# FLink_Unit.net
KiCad netlist of a schematic drawn in Altium Designer
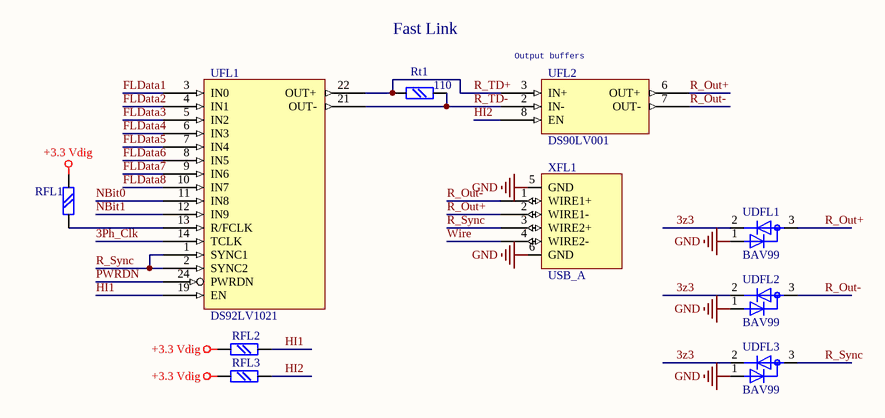
[diagram p0: FLink Unit.SchDoc]

(export (version "E")
  (design (tool "Eeschema 10.0.6"))
  (components
    (comp (ref "RFL1") (value "CHIP0805") (footprint "CHIP0805") (libsource (lib "*") (part "R")))
    (comp (ref "RFL2") (value "CHIP0805") (footprint "CHIP0805") (libsource (lib "*") (part "R")))
    (comp (ref "RFL3") (value "CHIP0805") (footprint "CHIP0805") (libsource (lib "*") (part "R")))
    (comp (ref "Rt1") (value "110") (footprint "CHIP0805") (libsource (lib "*") (part "R")))
    (comp (ref "UDFL1") (value "BAV99") (footprint "SOT-23") (libsource (lib "*") (part "BAV99")))
    (comp (ref "UDFL2") (value "BAV99") (footprint "SOT-23") (libsource (lib "*") (part "BAV99")))
    (comp (ref "UDFL3") (value "BAV99") (footprint "SOT-23") (libsource (lib "*") (part "BAV99")))
    (comp (ref "UFL1") (value "DS92LV1021") (footprint "28TSSOP") (libsource (lib "*") (part "DS92LV1021")))
    (comp (ref "UFL2") (value "DS90LV001") (footprint "Soic8_200") (libsource (lib "*") (part "DS90LV001")))
    (comp (ref "XFL1") (value "USB_A") (footprint "USB-A") (libsource (lib "*") (part "USB_A")))
  )
  (nets
    (net (code "1") (name "+3.3 Vdig") (class "Default")
      (node (ref "RFL1") (pin "2") (pinfunction "2_2") (pintype "passive"))
      (node (ref "RFL2") (pin "1") (pinfunction "1_1") (pintype "passive"))
      (node (ref "RFL3") (pin "1") (pinfunction "1_1") (pintype "passive"))
    )
    (net (code "2") (name "/3Ph_Clk") (class "Default")
      (node (ref "UFL1") (pin "14") (pinfunction "TCLK_14") (pintype "input"))
    )
    (net (code "3") (name "/3z3") (class "Default")
      (node (ref "UDFL1") (pin "2") (pinfunction "CATHODE_2") (pintype "passive"))
      (node (ref "UDFL2") (pin "2") (pinfunction "CATHODE_2") (pintype "passive"))
      (node (ref "UDFL3") (pin "2") (pinfunction "CATHODE_2") (pintype "passive"))
    )
    (net (code "4") (name "/FLData1") (class "Default")
      (node (ref "UFL1") (pin "3") (pinfunction "IN0_3") (pintype "input"))
    )
    (net (code "5") (name "/FLData2") (class "Default")
      (node (ref "UFL1") (pin "4") (pinfunction "IN1_4") (pintype "input"))
    )
    (net (code "6") (name "/FLData3") (class "Default")
      (node (ref "UFL1") (pin "5") (pinfunction "IN2_5") (pintype "input"))
    )
    (net (code "7") (name "/FLData4") (class "Default")
      (node (ref "UFL1") (pin "6") (pinfunction "IN3_6") (pintype "input"))
    )
    (net (code "8") (name "/FLData5") (class "Default")
      (node (ref "UFL1") (pin "7") (pinfunction "IN4_7") (pintype "input"))
    )
    (net (code "9") (name "/FLData6") (class "Default")
      (node (ref "UFL1") (pin "8") (pinfunction "IN5_8") (pintype "input"))
    )
    (net (code "10") (name "/FLData7") (class "Default")
      (node (ref "UFL1") (pin "9") (pinfunction "IN6_9") (pintype "input"))
    )
    (net (code "11") (name "/FLData8") (class "Default")
      (node (ref "UFL1") (pin "10") (pinfunction "IN7_10") (pintype "input"))
    )
    (net (code "12") (name "/HI1") (class "Default")
      (node (ref "RFL2") (pin "2") (pinfunction "2_2") (pintype "passive"))
      (node (ref "UFL1") (pin "19") (pinfunction "EN_19") (pintype "input"))
    )
    (net (code "13") (name "/HI2") (class "Default")
      (node (ref "RFL3") (pin "2") (pinfunction "2_2") (pintype "passive"))
      (node (ref "UFL2") (pin "8") (pinfunction "EN_8") (pintype "input"))
    )
    (net (code "14") (name "/NBit0") (class "Default")
      (node (ref "UFL1") (pin "11") (pinfunction "IN8_11") (pintype "input"))
    )
    (net (code "15") (name "/NBit1") (class "Default")
      (node (ref "UFL1") (pin "12") (pinfunction "IN9_12") (pintype "input"))
    )
    (net (code "16") (name "/PWRDN") (class "Default")
      (node (ref "UFL1") (pin "24") (pinfunction "PWRDN_24") (pintype "input"))
    )
    (net (code "17") (name "/R_Out+") (class "Default")
      (node (ref "UDFL1") (pin "3") (pinfunction "COMMON_3") (pintype "passive"))
      (node (ref "UFL2") (pin "6") (pinfunction "OUT+_6") (pintype "output"))
      (node (ref "XFL1") (pin "2") (pinfunction "WIRE1-_2") (pintype "bidirectional"))
    )
    (net (code "18") (name "/R_Out-") (class "Default")
      (node (ref "UDFL2") (pin "3") (pinfunction "COMMON_3") (pintype "passive"))
      (node (ref "UFL2") (pin "7") (pinfunction "OUT-_7") (pintype "output"))
      (node (ref "XFL1") (pin "1") (pinfunction "WIRE1+_1") (pintype "bidirectional"))
    )
    (net (code "19") (name "/R_Sync") (class "Default")
      (node (ref "UDFL3") (pin "3") (pinfunction "COMMON_3") (pintype "passive"))
      (node (ref "UFL1") (pin "1") (pinfunction "SYNC1_1") (pintype "input"))
      (node (ref "UFL1") (pin "2") (pinfunction "SYNC2_2") (pintype "input"))
      (node (ref "XFL1") (pin "3") (pinfunction "WIRE2+_3") (pintype "bidirectional"))
    )
    (net (code "20") (name "/R_TD+") (class "Default")
      (node (ref "Rt1") (pin "1") (pinfunction "1_1") (pintype "passive"))
      (node (ref "UFL1") (pin "22") (pinfunction "OUT+_22") (pintype "output"))
      (node (ref "UFL2") (pin "3") (pinfunction "IN+_3") (pintype "input"))
    )
    (net (code "21") (name "/R_TD-") (class "Default")
      (node (ref "Rt1") (pin "2") (pinfunction "2_2") (pintype "passive"))
      (node (ref "UFL1") (pin "21") (pinfunction "OUT-_21") (pintype "output"))
      (node (ref "UFL2") (pin "2") (pinfunction "IN-_2") (pintype "input"))
    )
    (net (code "22") (name "/Wire") (class "Default")
      (node (ref "XFL1") (pin "4") (pinfunction "WIRE2-_4") (pintype "bidirectional"))
    )
    (net (code "23") (name "AGND") (class "Default")
      (node (ref "UFL1") (pin "18") (pinfunction "AGND_18") (pintype "power_in"))
      (node (ref "UFL1") (pin "20") (pinfunction "AGND_20") (pintype "power_in"))
      (node (ref "UFL1") (pin "23") (pinfunction "AGND_23") (pintype "power_in"))
      (node (ref "UFL1") (pin "25") (pinfunction "AGND_25") (pintype "power_in"))
    )
    (net (code "24") (name "AVCC") (class "Default")
      (node (ref "UFL1") (pin "17") (pinfunction "AVCC_17") (pintype "power_in"))
      (node (ref "UFL1") (pin "26") (pinfunction "AVCC_26") (pintype "power_in"))
    )
    (net (code "25") (name "DGND") (class "Default")
      (node (ref "UFL1") (pin "15") (pinfunction "DGND_15") (pintype "power_in"))
      (node (ref "UFL1") (pin "16") (pinfunction "DGND_16") (pintype "power_in"))
    )
    (net (code "26") (name "DVCC") (class "Default")
      (node (ref "UFL1") (pin "27") (pinfunction "DVCC_27") (pintype "power_in"))
      (node (ref "UFL1") (pin "28") (pinfunction "DVCC_28") (pintype "power_in"))
    )
    (net (code "27") (name "GND") (class "Default")
      (node (ref "UDFL1") (pin "1") (pinfunction "ANODE_1") (pintype "passive"))
      (node (ref "UDFL2") (pin "1") (pinfunction "ANODE_1") (pintype "passive"))
      (node (ref "UDFL3") (pin "1") (pinfunction "ANODE_1") (pintype "passive"))
      (node (ref "UFL2") (pin "1") (pinfunction "GND_1") (pintype "power_in"))
      (node (ref "XFL1") (pin "5") (pinfunction "GND_5") (pintype "passive"))
      (node (ref "XFL1") (pin "6") (pinfunction "GND_6") (pintype "passive"))
    )
    (net (code "28") (name "Net-(UFL1-R{slash}FCLK)") (class "Default")
      (node (ref "RFL1") (pin "1") (pinfunction "1_1") (pintype "passive"))
      (node (ref "UFL1") (pin "13") (pinfunction "R/FCLK_13") (pintype "input"))
    )
    (net (code "29") (name "VCC") (class "Default")
      (node (ref "UFL2") (pin "5") (pinfunction "VCC_5") (pintype "power_in"))
    )
  )
)
